# ArduinoIO_R1.net
KiCad netlist of a schematic drawn in EasyEDA Pro
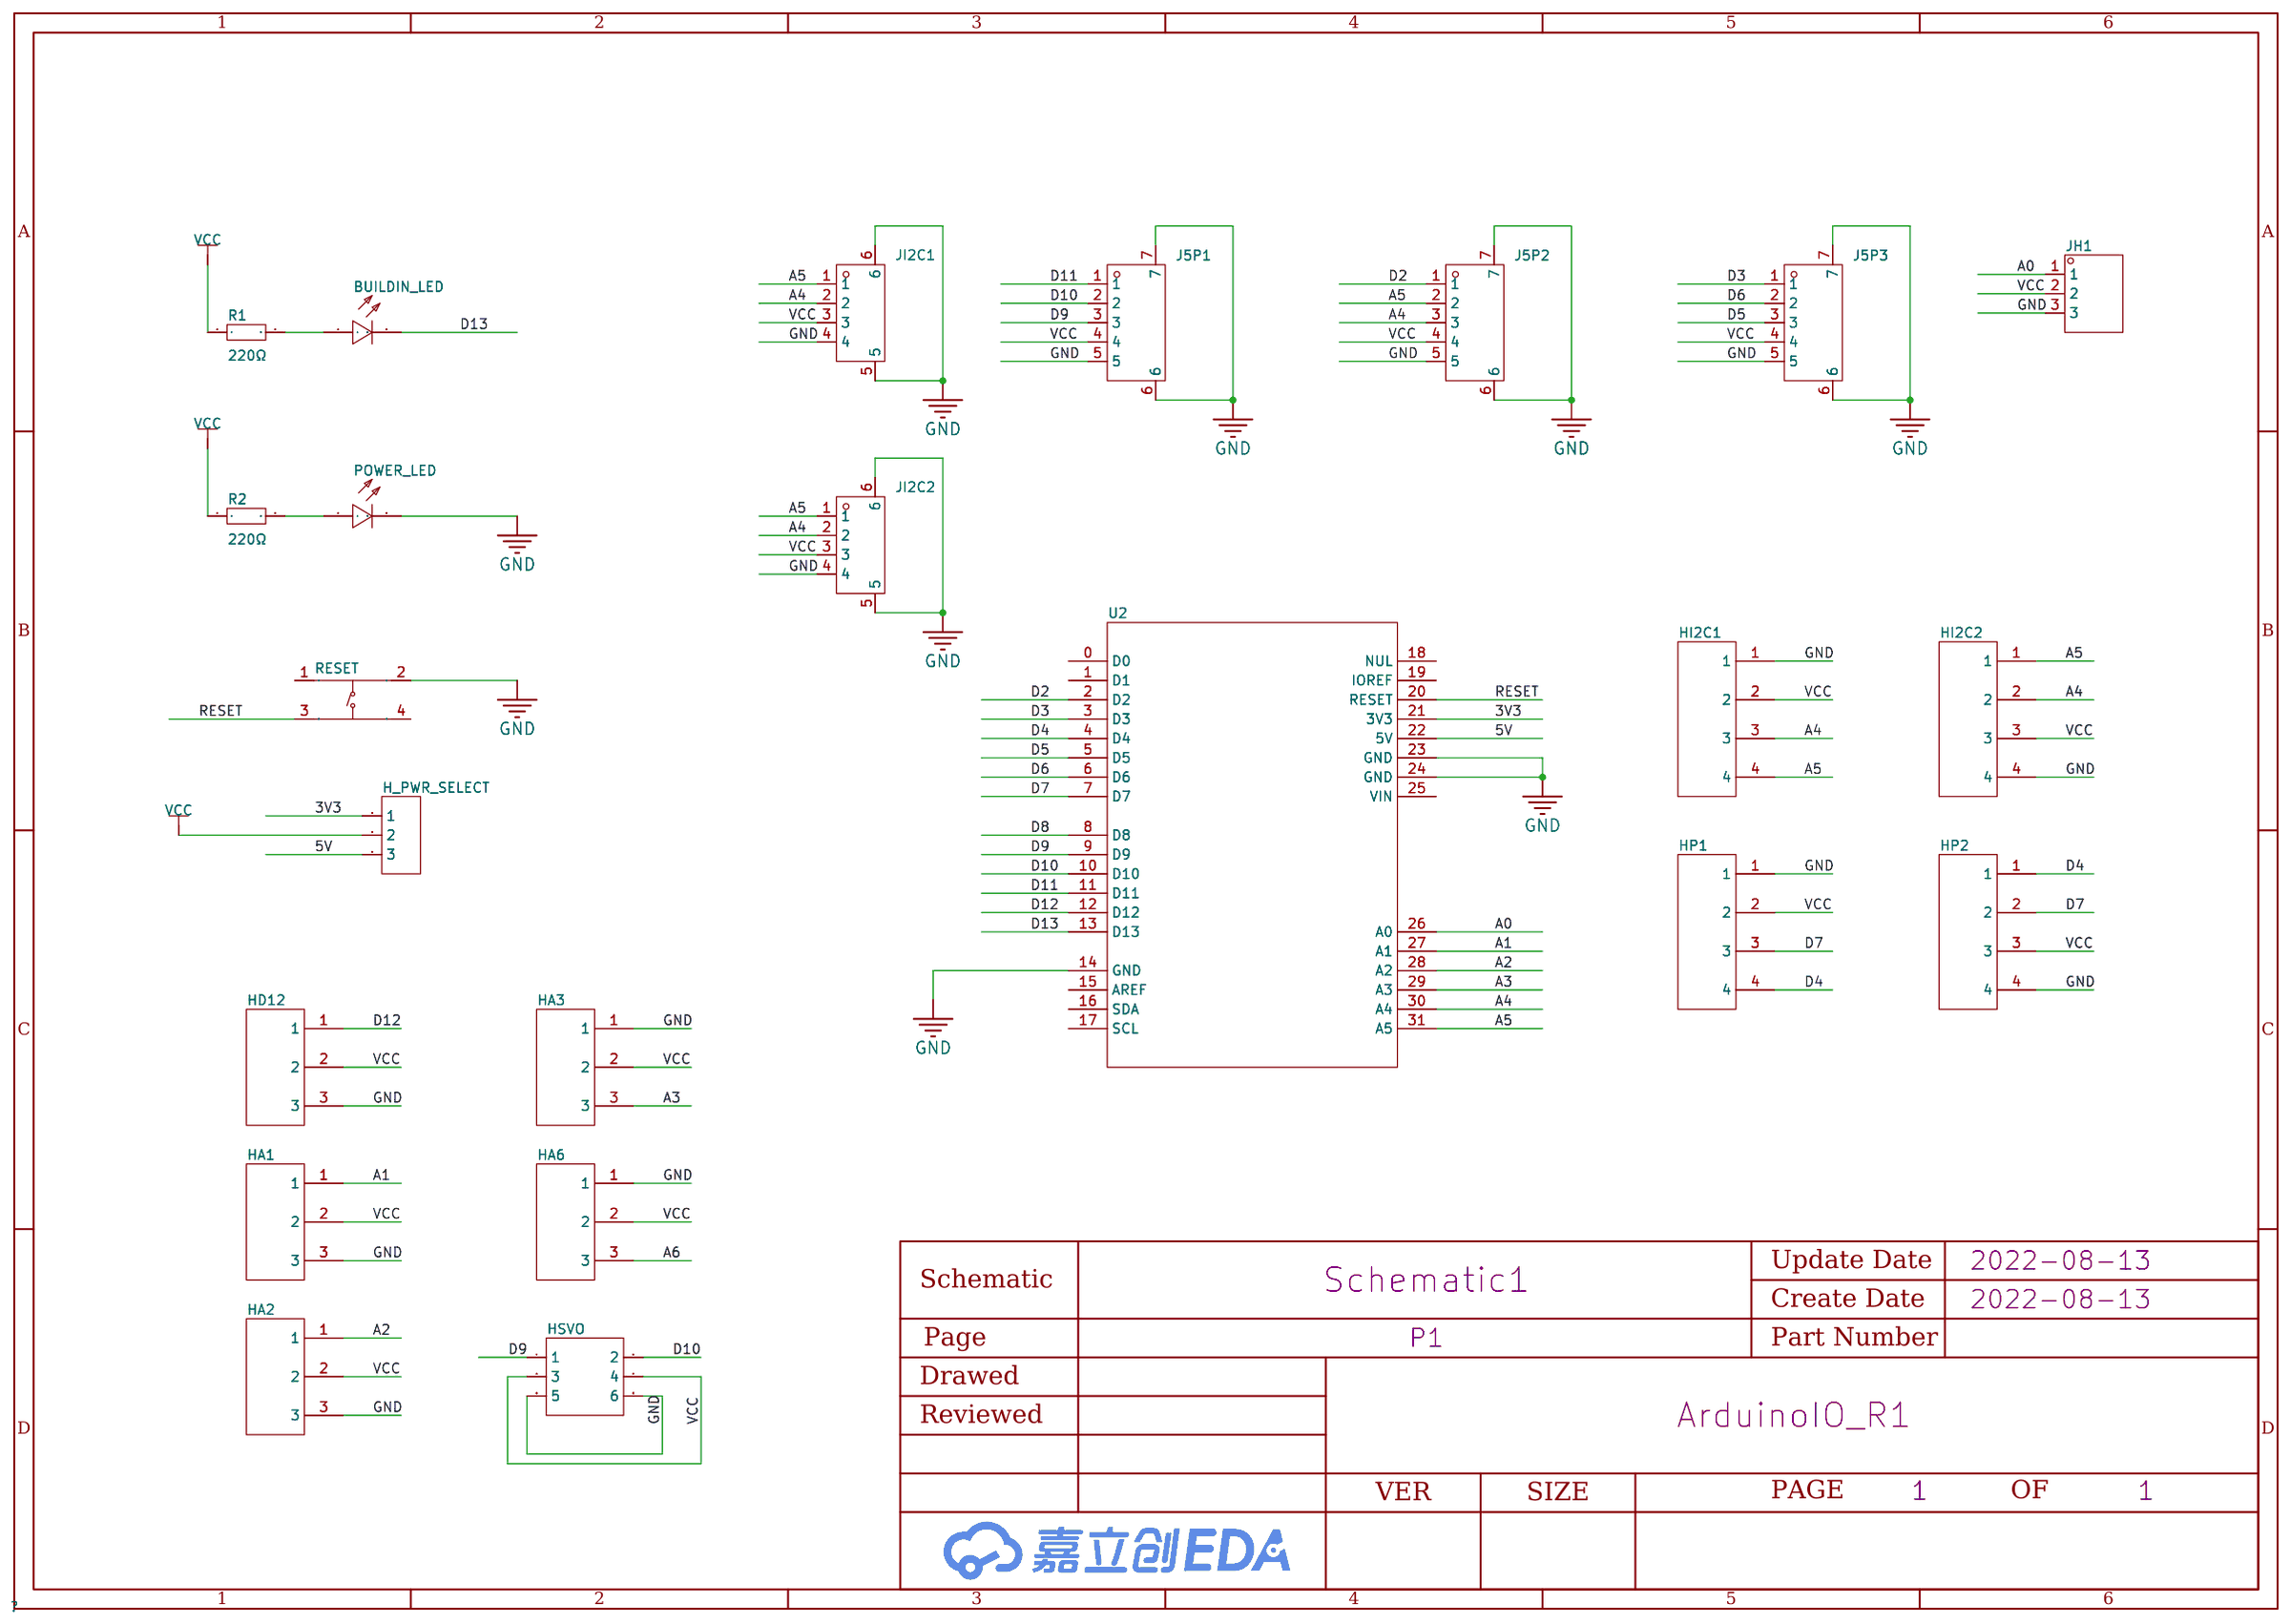
[diagram p0: schematic sheet]

(export (version "E")
  (design (tool "Eeschema 10.0.6"))
  (components
    (comp (ref "BUILDIN_LED")
      (value "~")
      (footprint "easyedapro:LED0603-R-RD")
      (description "照明颜色:翠绿;色温 - CCT（K）:-;主波长/色坐标:520~535nm;")
      (fields
        (field (name "Manufacturer Part") "19-217/GHC-YR1S2/3T")
        (field (name "Manufacturer") "EVERLIGHT(台湾亿光)")
      )
      (libsource (lib "easyedapro") (part "19-217/GHC-YR1S2/3T"))
    )
    (comp (ref "HA1")
      (value "~")
      (footprint "easyedapro:CONN-TH_B3B-PH-K-S")
      (description "参考系列:PH;间距:2mm;插针结构:1x3P;排数:1;每排PIN数:3;行距:-;安装方式:-;触头材质:黄铜;")
      (fields (field (name "Manufacturer Part") "B3B-PH-K-S(LF)(SN)") (field (name "Manufacturer") "JST"))
      (libsource (lib "easyedapro") (part "B3B-PH-K-S(LF)(SN)"))
    )
    (comp (ref "HA2")
      (value "~")
      (footprint "easyedapro:CONN-TH_B3B-PH-K-S")
      (description "参考系列:PH;间距:2mm;插针结构:1x3P;排数:1;每排PIN数:3;行距:-;安装方式:-;触头材质:黄铜;")
      (fields (field (name "Manufacturer Part") "B3B-PH-K-S(LF)(SN)") (field (name "Manufacturer") "JST"))
      (libsource (lib "easyedapro") (part "B3B-PH-K-S(LF)(SN)"))
    )
    (comp (ref "HA3")
      (value "~")
      (footprint "easyedapro:CONN-TH_B3B-PH-K-S")
      (description "参考系列:PH;间距:2mm;插针结构:1x3P;排数:1;每排PIN数:3;行距:-;安装方式:-;触头材质:黄铜;")
      (fields (field (name "Manufacturer Part") "B3B-PH-K-S(LF)(SN)") (field (name "Manufacturer") "JST"))
      (libsource (lib "easyedapro") (part "B3B-PH-K-S(LF)(SN)"))
    )
    (comp (ref "HA6")
      (value "~")
      (footprint "easyedapro:CONN-TH_B3B-PH-K-S")
      (description "参考系列:PH;间距:2mm;插针结构:1x3P;排数:1;每排PIN数:3;行距:-;安装方式:-;触头材质:黄铜;")
      (fields (field (name "Manufacturer Part") "B3B-PH-K-S(LF)(SN)") (field (name "Manufacturer") "JST"))
      (libsource (lib "easyedapro") (part "B3B-PH-K-S(LF)(SN)"))
    )
    (comp (ref "HD12")
      (value "~")
      (footprint "easyedapro:CONN-TH_B3B-PH-K-S")
      (description "参考系列:PH;间距:2mm;插针结构:1x3P;排数:1;每排PIN数:3;行距:-;安装方式:-;触头材质:黄铜;")
      (fields (field (name "Manufacturer Part") "B3B-PH-K-S(LF)(SN)") (field (name "Manufacturer") "JST"))
      (libsource (lib "easyedapro") (part "B3B-PH-K-S(LF)(SN)"))
    )
    (comp (ref "HI2C1")
      (value "~")
      (footprint "easyedapro:CONN-TH_B4B-PH-K-S")
      (description "参考系列:PH;间距:2mm;插针结构:1x4P;排数:1;每排PIN数:4;行距:-;安装方式:-;触头材质:黄铜;")
      (fields (field (name "Manufacturer Part") "B4B-PH-K-S(LF)(SN)") (field (name "Manufacturer") "JST"))
      (libsource (lib "easyedapro") (part "B4B-PH-K-S(LF)(SN)"))
    )
    (comp (ref "HI2C2")
      (value "~")
      (footprint "easyedapro:CONN-TH_B4B-PH-K-S")
      (description "参考系列:PH;间距:2mm;插针结构:1x4P;排数:1;每排PIN数:4;行距:-;安装方式:-;触头材质:黄铜;")
      (fields (field (name "Manufacturer Part") "B4B-PH-K-S(LF)(SN)") (field (name "Manufacturer") "JST"))
      (libsource (lib "easyedapro") (part "B4B-PH-K-S(LF)(SN)"))
    )
    (comp (ref "HP1")
      (value "~")
      (footprint "easyedapro:CONN-TH_B4B-PH-K-S")
      (description "参考系列:PH;间距:2mm;插针结构:1x4P;排数:1;每排PIN数:4;行距:-;安装方式:-;触头材质:黄铜;")
      (fields (field (name "Manufacturer Part") "B4B-PH-K-S(LF)(SN)") (field (name "Manufacturer") "JST"))
      (libsource (lib "easyedapro") (part "B4B-PH-K-S(LF)(SN)"))
    )
    (comp (ref "HP2")
      (value "~")
      (footprint "easyedapro:CONN-TH_B4B-PH-K-S")
      (description "参考系列:PH;间距:2mm;插针结构:1x4P;排数:1;每排PIN数:4;行距:-;安装方式:-;触头材质:黄铜;")
      (fields (field (name "Manufacturer Part") "B4B-PH-K-S(LF)(SN)") (field (name "Manufacturer") "JST"))
      (libsource (lib "easyedapro") (part "B4B-PH-K-S(LF)(SN)"))
    )
    (comp (ref "HSVO")
      (value "~")
      (footprint "easyedapro:HDR-TH_6P-P2.54-V-M-R2-C3-S2.54-1")
      (fields (field (name "Manufacturer Part") "2.54-2*3P针") (field (name "Manufacturer") "BOOMELE(博穆精密)"))
      (libsource (lib "easyedapro") (part "Header-Male-2.54_2x3"))
    )
    (comp (ref "H_PWR_SELECT")
      (value "~")
      (footprint "easyedapro:HDR-TH_3P-P2.54-V-M-1")
      (fields (field (name "Manufacturer Part") "2.54-1*3P针") (field (name "Manufacturer") "BOOMELE(博穆精密)"))
      (libsource (lib "easyedapro") (part "Header-Male-2.54_1x3"))
    )
    (comp (ref "J5P1")
      (value "~")
      (footprint "easyedapro:FPC-SMD_5P-P2.00_DEALON_PH-5PWB")
      (description "参考系列:-;间距:2mm;插针结构:1x5P;排数:1;每排PIN数:5;行距:-;公母:公型插针;安装方式:卧贴;额定电流:2A;工作温度范围:-25~+85;")
      (fields (field (name "Manufacturer Part") "PH-5PWB") (field (name "Manufacturer") "DEALON(德艺隆)"))
      (libsource (lib "easyedapro") (part "PH-5PWB"))
    )
    (comp (ref "J5P2")
      (value "~")
      (footprint "easyedapro:FPC-SMD_5P-P2.00_DEALON_PH-5PWB")
      (description "参考系列:-;间距:2mm;插针结构:1x5P;排数:1;每排PIN数:5;行距:-;公母:公型插针;安装方式:卧贴;额定电流:2A;工作温度范围:-25~+85;")
      (fields (field (name "Manufacturer Part") "PH-5PWB") (field (name "Manufacturer") "DEALON(德艺隆)"))
      (libsource (lib "easyedapro") (part "PH-5PWB"))
    )
    (comp (ref "J5P3")
      (value "~")
      (footprint "easyedapro:FPC-SMD_5P-P2.00_DEALON_PH-5PWB")
      (description "参考系列:-;间距:2mm;插针结构:1x5P;排数:1;每排PIN数:5;行距:-;公母:公型插针;安装方式:卧贴;额定电流:2A;工作温度范围:-25~+85;")
      (fields (field (name "Manufacturer Part") "PH-5PWB") (field (name "Manufacturer") "DEALON(德艺隆)"))
      (libsource (lib "easyedapro") (part "PH-5PWB"))
    )
    (comp (ref "JH1")
      (value "~")
      (footprint "easyedapro:HDR-TH_3P-P2.54-V-M-1")
      (fields (field (name "Manufacturer Part") "77311-102-03LF") (field (name "Manufacturer") "Amphenol"))
      (libsource (lib "easyedapro") (part "77311-102-03LF"))
    )
    (comp (ref "JI2C1")
      (value "~")
      (footprint "easyedapro:CONN-SMD_4P-P2.00_HDGC_HDGC2001WR-S-4P")
      (description "参考系列:PH;间距:2mm;插针结构:1x4P;排数:1;每排PIN数:4;行距:-;公母:公型插针;安装方式:卧贴;额定电流:5A;工作温度范围:-25~+70;")
      (fields (field (name "Manufacturer Part") "HDGC2001WR-S-4P") (field (name "Manufacturer") "HDGC(华德共创)"))
      (libsource (lib "easyedapro") (part "HDGC2001WR-S-4P"))
    )
    (comp (ref "JI2C2")
      (value "~")
      (footprint "easyedapro:CONN-SMD_4P-P2.00_HDGC_HDGC2001WR-S-4P")
      (description "参考系列:PH;间距:2mm;插针结构:1x4P;排数:1;每排PIN数:4;行距:-;公母:公型插针;安装方式:卧贴;额定电流:5A;工作温度范围:-25~+70;")
      (fields (field (name "Manufacturer Part") "HDGC2001WR-S-4P") (field (name "Manufacturer") "HDGC(华德共创)"))
      (libsource (lib "easyedapro") (part "HDGC2001WR-S-4P"))
    )
    (comp (ref "POWER_LED")
      (value "~")
      (footprint "easyedapro:LED0603-R-RD")
      (description "照明颜色:翠绿;色温 - CCT（K）:-;主波长/色坐标:520~535nm;")
      (fields
        (field (name "Manufacturer Part") "19-217/GHC-YR1S2/3T")
        (field (name "Manufacturer") "EVERLIGHT(台湾亿光)")
      )
      (libsource (lib "easyedapro") (part "19-217/GHC-YR1S2/3T"))
    )
    (comp (ref "R1")
      (value "220Ω")
      (footprint "easyedapro:R0603")
      (description "阻值:10kΩ;精度:±0.1%;温度系数:±25ppm/;功率:100mW;工作温度范围:-55~+155;电阻类型:薄膜电阻;最大工作电压:75V;")
      (fields
        (field (name "Manufacturer Part") "TR0603B10K0P0525Z")
        (field (name "Manufacturer") "EVER OHMS(天二科技)")
      )
      (libsource (lib "easyedapro") (part "TR0603B10KP05250.1W"))
    )
    (comp (ref "R2")
      (value "220Ω")
      (footprint "easyedapro:R0603")
      (description "阻值:10kΩ;精度:±0.1%;温度系数:±25ppm/;功率:100mW;工作温度范围:-55~+155;电阻类型:薄膜电阻;最大工作电压:75V;")
      (fields
        (field (name "Manufacturer Part") "TR0603B10K0P0525Z")
        (field (name "Manufacturer") "EVER OHMS(天二科技)")
      )
      (libsource (lib "easyedapro") (part "TR0603B10KP05250.1W"))
    )
    (comp (ref "RESET")
      (value "~")
      (footprint "easyedapro:SW-TH_4P-L6.0-W6.0-P4.50-LS6.5")
      (description "触点电流:50mA;额定电压(DC):12V;电路结构:单刀单掷;安装方式:直插;按钮形状:圆形按钮;带灯:-;开关长度:6mm;开关宽度:6mm;开关高度:5mm;")
      (fields (field (name "Manufacturer Part") "TS665CJ") (field (name "Manufacturer") "SHOU HAN(首韩)"))
      (libsource (lib "easyedapro") (part "TS665CJ"))
    )
    (comp (ref "U2")
      (value "~")
      (footprint "easyedapro:ARDUINO_UNO_SHEILD")
      (libsource (lib "easyedapro") (part "ARDUINO_UNO"))
    )
  )
  (nets
    (net (code "1") (name "/3V3") (class "Default")
      (node (ref "H_PWR_SELECT") (pin "1") (pinfunction "1_1") (pintype "input"))
      (node (ref "U2") (pin "21") (pinfunction "3V3_21") (pintype "input"))
    )
    (net (code "2") (name "/5V") (class "Default")
      (node (ref "H_PWR_SELECT") (pin "3") (pinfunction "3_3") (pintype "input"))
      (node (ref "U2") (pin "22") (pinfunction "5V_22") (pintype "input"))
    )
    (net (code "3") (name "/A0") (class "Default")
      (node (ref "JH1") (pin "1") (pinfunction "1_1") (pintype "input"))
      (node (ref "U2") (pin "26") (pinfunction "A0_26") (pintype "input"))
    )
    (net (code "4") (name "/A1") (class "Default")
      (node (ref "HA1") (pin "1") (pinfunction "1_1") (pintype "input"))
      (node (ref "U2") (pin "27") (pinfunction "A1_27") (pintype "input"))
    )
    (net (code "5") (name "/A2") (class "Default")
      (node (ref "HA2") (pin "1") (pinfunction "1_1") (pintype "input"))
      (node (ref "U2") (pin "28") (pinfunction "A2_28") (pintype "input"))
    )
    (net (code "6") (name "/A3") (class "Default")
      (node (ref "HA3") (pin "3") (pinfunction "3_3") (pintype "input"))
      (node (ref "U2") (pin "29") (pinfunction "A3_29") (pintype "input"))
    )
    (net (code "7") (name "/A4") (class "Default")
      (node (ref "HI2C1") (pin "3") (pinfunction "3_3") (pintype "input"))
      (node (ref "HI2C2") (pin "2") (pinfunction "2_2") (pintype "input"))
      (node (ref "J5P2") (pin "3") (pinfunction "3_3") (pintype "input"))
      (node (ref "JI2C1") (pin "2") (pinfunction "2_2") (pintype "input"))
      (node (ref "JI2C2") (pin "2") (pinfunction "2_2") (pintype "input"))
      (node (ref "U2") (pin "30") (pinfunction "A4_30") (pintype "input"))
    )
    (net (code "8") (name "/A5") (class "Default")
      (node (ref "HI2C1") (pin "4") (pinfunction "4_4") (pintype "input"))
      (node (ref "HI2C2") (pin "1") (pinfunction "1_1") (pintype "input"))
      (node (ref "J5P2") (pin "2") (pinfunction "2_2") (pintype "input"))
      (node (ref "JI2C1") (pin "1") (pinfunction "1_1") (pintype "input"))
      (node (ref "JI2C2") (pin "1") (pinfunction "1_1") (pintype "input"))
      (node (ref "U2") (pin "31") (pinfunction "A5_31") (pintype "input"))
    )
    (net (code "9") (name "/A6") (class "Default")
      (node (ref "HA6") (pin "3") (pinfunction "3_3") (pintype "input"))
    )
    (net (code "10") (name "/D2") (class "Default")
      (node (ref "J5P2") (pin "1") (pinfunction "1_1") (pintype "input"))
      (node (ref "U2") (pin "2") (pinfunction "D2_2") (pintype "input"))
    )
    (net (code "11") (name "/D3") (class "Default")
      (node (ref "J5P3") (pin "1") (pinfunction "1_1") (pintype "input"))
      (node (ref "U2") (pin "3") (pinfunction "D3_3") (pintype "input"))
    )
    (net (code "12") (name "/D4") (class "Default")
      (node (ref "HP1") (pin "4") (pinfunction "4_4") (pintype "input"))
      (node (ref "HP2") (pin "1") (pinfunction "1_1") (pintype "input"))
      (node (ref "U2") (pin "4") (pinfunction "D4_4") (pintype "input"))
    )
    (net (code "13") (name "/D5") (class "Default")
      (node (ref "J5P3") (pin "3") (pinfunction "3_3") (pintype "input"))
      (node (ref "U2") (pin "5") (pinfunction "D5_5") (pintype "input"))
    )
    (net (code "14") (name "/D6") (class "Default")
      (node (ref "J5P3") (pin "2") (pinfunction "2_2") (pintype "input"))
      (node (ref "U2") (pin "6") (pinfunction "D6_6") (pintype "input"))
    )
    (net (code "15") (name "/D7") (class "Default")
      (node (ref "HP1") (pin "3") (pinfunction "3_3") (pintype "input"))
      (node (ref "HP2") (pin "2") (pinfunction "2_2") (pintype "input"))
      (node (ref "U2") (pin "7") (pinfunction "D7_7") (pintype "input"))
    )
    (net (code "16") (name "/D8") (class "Default")
      (node (ref "U2") (pin "8") (pinfunction "D8_8") (pintype "input"))
    )
    (net (code "17") (name "/D9") (class "Default")
      (node (ref "HSVO") (pin "1") (pinfunction "1_1") (pintype "input"))
      (node (ref "J5P1") (pin "3") (pinfunction "3_3") (pintype "input"))
      (node (ref "U2") (pin "9") (pinfunction "D9_9") (pintype "input"))
    )
    (net (code "18") (name "/D10") (class "Default")
      (node (ref "HSVO") (pin "2") (pinfunction "2_2") (pintype "input"))
      (node (ref "J5P1") (pin "2") (pinfunction "2_2") (pintype "input"))
      (node (ref "U2") (pin "10") (pinfunction "D10_10") (pintype "input"))
    )
    (net (code "19") (name "/D11") (class "Default")
      (node (ref "J5P1") (pin "1") (pinfunction "1_1") (pintype "input"))
      (node (ref "U2") (pin "11") (pinfunction "D11_11") (pintype "input"))
    )
    (net (code "20") (name "/D12") (class "Default")
      (node (ref "HD12") (pin "1") (pinfunction "1_1") (pintype "input"))
      (node (ref "U2") (pin "12") (pinfunction "D12_12") (pintype "input"))
    )
    (net (code "21") (name "/D13") (class "Default")
      (node (ref "BUILDIN_LED") (pin "2") (pinfunction "C_2") (pintype "input"))
      (node (ref "U2") (pin "13") (pinfunction "D13_13") (pintype "input"))
    )
    (net (code "22") (name "/RESET") (class "Default")
      (node (ref "RESET") (pin "3") (pinfunction "C_3") (pintype "input"))
      (node (ref "U2") (pin "20") (pinfunction "RESET_20") (pintype "input"))
    )
    (net (code "23") (name "GND") (class "Default")
      (node (ref "HA1") (pin "3") (pinfunction "3_3") (pintype "input"))
      (node (ref "HA2") (pin "3") (pinfunction "3_3") (pintype "input"))
      (node (ref "HA3") (pin "1") (pinfunction "1_1") (pintype "input"))
      (node (ref "HA6") (pin "1") (pinfunction "1_1") (pintype "input"))
      (node (ref "HD12") (pin "3") (pinfunction "3_3") (pintype "input"))
      (node (ref "HI2C1") (pin "1") (pinfunction "1_1") (pintype "input"))
      (node (ref "HI2C2") (pin "4") (pinfunction "4_4") (pintype "input"))
      (node (ref "HP1") (pin "1") (pinfunction "1_1") (pintype "input"))
      (node (ref "HP2") (pin "4") (pinfunction "4_4") (pintype "input"))
      (node (ref "HSVO") (pin "5") (pinfunction "5_5") (pintype "input"))
      (node (ref "HSVO") (pin "6") (pinfunction "6_6") (pintype "input"))
      (node (ref "J5P1") (pin "5") (pinfunction "5_5") (pintype "input"))
      (node (ref "J5P1") (pin "6") (pinfunction "6_6") (pintype "input"))
      (node (ref "J5P1") (pin "7") (pinfunction "7_7") (pintype "input"))
      (node (ref "J5P2") (pin "5") (pinfunction "5_5") (pintype "input"))
      (node (ref "J5P2") (pin "6") (pinfunction "6_6") (pintype "input"))
      (node (ref "J5P2") (pin "7") (pinfunction "7_7") (pintype "input"))
      (node (ref "J5P3") (pin "5") (pinfunction "5_5") (pintype "input"))
      (node (ref "J5P3") (pin "6") (pinfunction "6_6") (pintype "input"))
      (node (ref "J5P3") (pin "7") (pinfunction "7_7") (pintype "input"))
      (node (ref "JH1") (pin "3") (pinfunction "3_3") (pintype "input"))
      (node (ref "JI2C1") (pin "4") (pinfunction "4_4") (pintype "input"))
      (node (ref "JI2C1") (pin "5") (pinfunction "5_5") (pintype "input"))
      (node (ref "JI2C1") (pin "6") (pinfunction "6_6") (pintype "input"))
      (node (ref "JI2C2") (pin "4") (pinfunction "4_4") (pintype "input"))
      (node (ref "JI2C2") (pin "5") (pinfunction "5_5") (pintype "input"))
      (node (ref "JI2C2") (pin "6") (pinfunction "6_6") (pintype "input"))
      (node (ref "POWER_LED") (pin "2") (pinfunction "C_2") (pintype "input"))
      (node (ref "RESET") (pin "2") (pinfunction "B_2") (pintype "input"))
      (node (ref "U2") (pin "14") (pinfunction "GND_14") (pintype "input"))
      (node (ref "U2") (pin "23") (pinfunction "GND_23") (pintype "input"))
      (node (ref "U2") (pin "24") (pinfunction "GND_24") (pintype "input"))
    )
    (net (code "24") (name "Net-(BUILDIN_LED-A)") (class "Default")
      (node (ref "BUILDIN_LED") (pin "1") (pinfunction "A_1") (pintype "input"))
      (node (ref "R1") (pin "2") (pinfunction "2_2") (pintype "input"))
    )
    (net (code "25") (name "Net-(POWER_LED-A)") (class "Default")
      (node (ref "POWER_LED") (pin "1") (pinfunction "A_1") (pintype "input"))
      (node (ref "R2") (pin "2") (pinfunction "2_2") (pintype "input"))
    )
    (net (code "26") (name "VCC") (class "Default")
      (node (ref "HA1") (pin "2") (pinfunction "2_2") (pintype "input"))
      (node (ref "HA2") (pin "2") (pinfunction "2_2") (pintype "input"))
      (node (ref "HA3") (pin "2") (pinfunction "2_2") (pintype "input"))
      (node (ref "HA6") (pin "2") (pinfunction "2_2") (pintype "input"))
      (node (ref "HD12") (pin "2") (pinfunction "2_2") (pintype "input"))
      (node (ref "HI2C1") (pin "2") (pinfunction "2_2") (pintype "input"))
      (node (ref "HI2C2") (pin "3") (pinfunction "3_3") (pintype "input"))
      (node (ref "HP1") (pin "2") (pinfunction "2_2") (pintype "input"))
      (node (ref "HP2") (pin "3") (pinfunction "3_3") (pintype "input"))
      (node (ref "HSVO") (pin "3") (pinfunction "3_3") (pintype "input"))
      (node (ref "HSVO") (pin "4") (pinfunction "4_4") (pintype "input"))
      (node (ref "H_PWR_SELECT") (pin "2") (pinfunction "2_2") (pintype "input"))
      (node (ref "J5P1") (pin "4") (pinfunction "4_4") (pintype "input"))
      (node (ref "J5P2") (pin "4") (pinfunction "4_4") (pintype "input"))
      (node (ref "J5P3") (pin "4") (pinfunction "4_4") (pintype "input"))
      (node (ref "JH1") (pin "2") (pinfunction "2_2") (pintype "input"))
      (node (ref "JI2C1") (pin "3") (pinfunction "3_3") (pintype "input"))
      (node (ref "JI2C2") (pin "3") (pinfunction "3_3") (pintype "input"))
      (node (ref "R1") (pin "1") (pinfunction "1_1") (pintype "input"))
      (node (ref "R2") (pin "1") (pinfunction "1_1") (pintype "input"))
    )
    (net (code "27") (name "unconnected-(RESET-A-Pad1)") (class "Default")
      (node (ref "RESET") (pin "1") (pinfunction "A_1") (pintype "input"))
    )
    (net (code "28") (name "unconnected-(RESET-D-Pad4)") (class "Default")
      (node (ref "RESET") (pin "4") (pinfunction "D_4") (pintype "input"))
    )
    (net (code "29") (name "unconnected-(U2-AREF-Pad15)") (class "Default")
      (node (ref "U2") (pin "15") (pinfunction "AREF_15") (pintype "input"))
    )
    (net (code "30") (name "unconnected-(U2-D0-Pad0)") (class "Default")
      (node (ref "U2") (pin "0") (pinfunction "D0_0") (pintype "input"))
    )
    (net (code "31") (name "unconnected-(U2-D1-Pad1)") (class "Default")
      (node (ref "U2") (pin "1") (pinfunction "D1_1") (pintype "input"))
    )
    (net (code "32") (name "unconnected-(U2-IOREF-Pad19)") (class "Default")
      (node (ref "U2") (pin "19") (pinfunction "IOREF_19") (pintype "input"))
    )
    (net (code "33") (name "unconnected-(U2-NUL-Pad18)") (class "Default")
      (node (ref "U2") (pin "18") (pinfunction "NUL_18") (pintype "input"))
    )
    (net (code "34") (name "unconnected-(U2-SCL-Pad17)") (class "Default")
      (node (ref "U2") (pin "17") (pinfunction "SCL_17") (pintype "input"))
    )
    (net (code "35") (name "unconnected-(U2-SDA-Pad16)") (class "Default")
      (node (ref "U2") (pin "16") (pinfunction "SDA_16") (pintype "input"))
    )
    (net (code "36") (name "unconnected-(U2-VIN-Pad25)") (class "Default")
      (node (ref "U2") (pin "25") (pinfunction "VIN_25") (pintype "input"))
    )
  )
)
